# Sheet2.net
KiCad netlist of a schematic drawn in Altium Designer
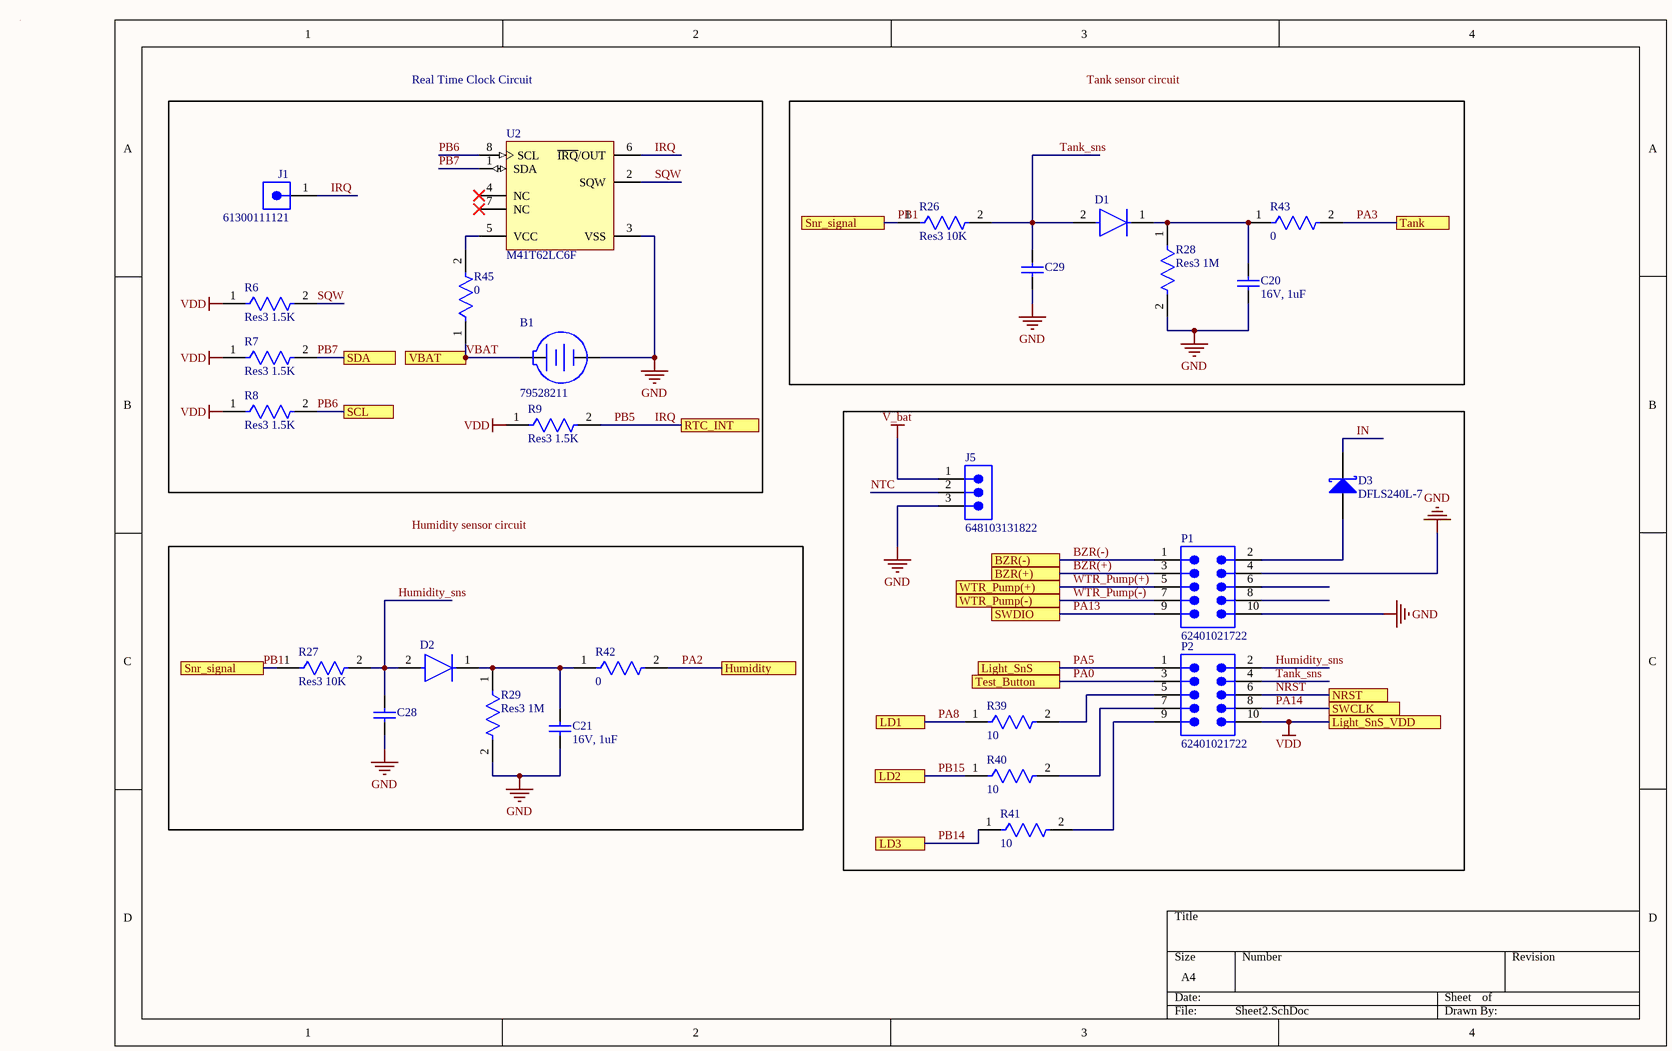
[diagram p0: Sheet2.SchDoc]

(export (version "E")
  (design (tool "Eeschema 10.0.6"))
  (components
    (comp (ref "B1")
      (value "79528211")
      (footprint "79528211")
      (description "Battery Holder, 2025/2032, Th Rohs Compliant: Yes")
      (libsource (lib "Altium Content Vault") (part "Battery Holder"))
    )
    (comp (ref "C20")
      (value "16V, 1uF")
      (footprint "CAPC1608X90X35NL15T15")
      (fields
        (field (name "MANUFACTURER") "AVX Interconnect / Elco")
        (field (name "PART NUMBER") "0603YC105JAT2A")
      )
      (libsource (lib "Altium Content Vault") (part "CAP"))
    )
    (comp (ref "C21")
      (value "16V, 1uF")
      (footprint "CAPC1608X90X35NL15T15")
      (fields
        (field (name "MANUFACTURER") "AVX Interconnect / Elco")
        (field (name "PART NUMBER") "0603YC105JAT2A")
      )
      (libsource (lib "Altium Content Vault") (part "CAP"))
    )
    (comp (ref "C28")
      (value "16V, 1uF")
      (footprint "CAPC1608X90X35NL15T15")
      (fields
        (field (name "MANUFACTURER") "AVX Interconnect / Elco")
        (field (name "PART NUMBER") "0603YC105JAT2A")
      )
      (libsource (lib "Altium Content Vault") (part "CAP"))
    )
    (comp (ref "C29")
      (value "16V, 1uF")
      (footprint "CAPC1608X90X35NL15T15")
      (fields
        (field (name "MANUFACTURER") "AVX Interconnect / Elco")
        (field (name "PART NUMBER") "0603YC105JAT2A")
      )
      (libsource (lib "Altium Content Vault") (part "CAP"))
    )
    (comp (ref "D1")
      (value "1N4148WS-HG3-08")
      (footprint "FP-S8-V-3910_02-001-MFG")
      (description "DIODE GEN PURP 100V 150MA SOD323")
      (libsource (lib "Altium Content Vault") (part "d7152d700b627762746794eb795d46e"))
    )
    (comp (ref "D2")
      (value "1N4148WS-HG3-08")
      (footprint "FP-S8-V-3910_02-001-MFG")
      (description "DIODE GEN PURP 100V 150MA SOD323")
      (libsource (lib "Altium Content Vault") (part "d7152d700b627762746794eb795d46e"))
    )
    (comp (ref "D3")
      (value "DFLS240L-7")
      (footprint "DIOD-POWERDI123-2_A_V")
      (description "Low VF Schottky Barrier Rectifier, 2 A, 40 V, -55 to 125 degC, 2-Pin SMD, RoHS, Tape and Reel")
      (fields (field (name "MANUFACTURER") "Diodes Inc"))
      (libsource (lib "Altium Content Vault") (part "DSKY-AK-2"))
    )
    (comp (ref "J1")
      (value "61300111121")
      (footprint "61300111121")
      (description "THT Vertical Pin Header WR-PHD, Pitch 2.54 mm, Single Row, 1 pins")
      (libsource (lib "Altium Content Vault") (part "Header_Male_1R_01P"))
    )
    (comp (ref "J5")
      (value "648103131822")
      (footprint "648103131822")
      (description "Wr-wtb; 1.5MM Pitch 3 Way 1 Row Shrouded Straight Pcb Header, Through Hole")
      (libsource (lib "Altium Content Vault") (part "Header_Male_1R_03P"))
    )
    (comp (ref "P1")
      (value "62401021722")
      (footprint "62401021722")
      (description "WR-WTB Wire-to-Board Connectors 2.00 mm")
      (libsource (lib "Altium Content Vault") (part "Header_Male_2R_10P"))
    )
    (comp (ref "P2")
      (value "62401021722")
      (footprint "62401021722")
      (description "WR-WTB Wire-to-Board Connectors 2.00 mm")
      (libsource (lib "Altium Content Vault") (part "Header_Male_2R_10P"))
    )
    (comp (ref "R6")
      (value "Res3 1.5K")
      (footprint "FP-AC0603-IPC_B")
      (description "RES 1.5kΩ 1.00% 0.2W 0603")
      (libsource (lib "Altium Content Vault") (part "1029c3af85768c4190bb7ad29bc67b5"))
    )
    (comp (ref "R7")
      (value "Res3 1.5K")
      (footprint "FP-AC0603-MFG")
      (description "RES 1.5kΩ 1.00% 0.2W 0603")
      (libsource (lib "Altium Content Vault") (part "1029c3af85768c4190bb7ad29bc67b5"))
    )
    (comp (ref "R8")
      (value "Res3 1.5K")
      (footprint "FP-AC0603-MFG")
      (description "RES 1.5kΩ 1.00% 0.2W 0603")
      (libsource (lib "Altium Content Vault") (part "1029c3af85768c4190bb7ad29bc67b5"))
    )
    (comp (ref "R9")
      (value "Res3 1.5K")
      (footprint "FP-AC0603-MFG")
      (description "RES 1.5kΩ 1.00% 0.2W 0603")
      (libsource (lib "Altium Content Vault") (part "1029c3af85768c4190bb7ad29bc67b5"))
    )
    (comp (ref "R26")
      (value "Res3 10K")
      (footprint "FP-AC0603-MFG")
      (description "RES 10kΩ 1.00% 0.2W 0603")
      (libsource (lib "Altium Content Vault") (part "1029c3af85768c4190bb7ad29bc67b5"))
    )
    (comp (ref "R27")
      (value "Res3 10K")
      (footprint "FP-AC0603-MFG")
      (description "RES 10kΩ 1.00% 0.2W 0603")
      (libsource (lib "Altium Content Vault") (part "1029c3af85768c4190bb7ad29bc67b5"))
    )
    (comp (ref "R28")
      (value "Res3 1M")
      (footprint "FP-CRGP0603-IPC_C")
      (description "RES 1M OHM 1% 1/4W 0603")
      (fields (field (name "TOLERANCE") "1%"))
      (libsource (lib "Altium Content Vault") (part "1029c3af85768c4190bb7ad29bc67b5"))
    )
    (comp (ref "R29")
      (value "Res3 1M")
      (footprint "FP-CRGP0603-IPC_C")
      (description "RES 1M OHM 1% 1/4W 0603")
      (fields (field (name "TOLERANCE") "1%"))
      (libsource (lib "Altium Content Vault") (part "1029c3af85768c4190bb7ad29bc67b5"))
    )
    (comp (ref "R39")
      (value "10")
      (footprint "FP-AC0603-MFG")
      (description "RES 10kΩ 5.00% 0.1W 0603")
      (fields (field (name "TOLERANCE") "5%"))
      (libsource (lib "Altium Content Vault") (part "1029c3af85768c4190bb7ad29bc67b5"))
    )
    (comp (ref "R40")
      (value "10")
      (footprint "FP-AC0603-MFG")
      (description "RES 10kΩ 5.00% 0.1W 0603")
      (fields (field (name "TOLERANCE") "5%"))
      (libsource (lib "Altium Content Vault") (part "1029c3af85768c4190bb7ad29bc67b5"))
    )
    (comp (ref "R41")
      (value "10")
      (footprint "FP-AC0603-MFG")
      (description "RES 10kΩ 5.00% 0.1W 0603")
      (fields (field (name "TOLERANCE") "5%"))
      (libsource (lib "Altium Content Vault") (part "1029c3af85768c4190bb7ad29bc67b5"))
    )
    (comp (ref "R42")
      (value "0")
      (footprint "FP-CRCW0603-MFG")
      (description "RES SMD 0 OHM JUMPER 1/10W 0603")
      (fields (field (name "TOLERANCE") "5%"))
      (libsource (lib "Altium Content Vault") (part "1029c3af85768c4190bb7ad29bc67b5"))
    )
    (comp (ref "R43")
      (value "0")
      (footprint "FP-CRCW0603-MFG")
      (description "RES SMD 0 OHM JUMPER 1/10W 0603")
      (fields (field (name "TOLERANCE") "5%"))
      (libsource (lib "Altium Content Vault") (part "1029c3af85768c4190bb7ad29bc67b5"))
    )
    (comp (ref "R45")
      (value "0")
      (footprint "FP-CRCW0603-MFG")
      (description "RES SMD 0 OHM JUMPER 1/10W 0603")
      (fields (field (name "TOLERANCE") "5%"))
      (libsource (lib "Altium Content Vault") (part "1029c3af85768c4190bb7ad29bc67b5"))
    )
    (comp (ref "U2")
      (value "M41T62LC6F")
      (footprint "STM-LCC8_V")
      (fields (field (name "MANUFACTURER") "STMicroelectronics"))
      (libsource (lib "Altium Content Vault") (part "STM-M41T62-LCC8"))
    )
  )
  (nets
    (net (code "1") (name "/BZR(+)") (class "Default")
      (node (ref "P1") (pin "3") (pinfunction "3_3") (pintype "passive"))
    )
    (net (code "2") (name "/BZR(-)") (class "Default")
      (node (ref "P1") (pin "1") (pinfunction "1_1") (pintype "passive"))
    )
    (net (code "4") (name "/Humidity_sns") (class "Default")
      (node (ref "C28") (pin "2") (pinfunction "2_2") (pintype "passive"))
      (node (ref "D2") (pin "2") (pinfunction "A_2") (pintype "passive"))
      (node (ref "P2") (pin "2") (pinfunction "2_2") (pintype "passive"))
      (node (ref "R27") (pin "2") (pinfunction "2_2") (pintype "passive"))
    )
    (net (code "5") (name "/IN") (class "Default")
      (node (ref "D3") (pin "2") (pinfunction "K_2") (pintype "passive"))
    )
    (net (code "6") (name "/IRQ") (class "Default")
      (node (ref "J1") (pin "1") (pinfunction "1_1") (pintype "passive"))
      (node (ref "R9") (pin "2") (pinfunction "2_2") (pintype "passive"))
      (node (ref "U2") (pin "6") (pinfunction "~{IRQ}/OUT_6") (pintype "passive"))
    )
    (net (code "7") (name "/NRST") (class "Default")
      (node (ref "P2") (pin "6") (pinfunction "6_6") (pintype "passive"))
    )
    (net (code "8") (name "/NTC") (class "Default")
      (node (ref "J5") (pin "2") (pinfunction "2_2") (pintype "passive"))
    )
    (net (code "9") (name "/PA0") (class "Default")
      (node (ref "P2") (pin "3") (pinfunction "3_3") (pintype "passive"))
    )
    (net (code "10") (name "/PA2") (class "Default")
      (node (ref "R42") (pin "2") (pinfunction "2_2") (pintype "passive"))
    )
    (net (code "11") (name "/PA3") (class "Default")
      (node (ref "R43") (pin "2") (pinfunction "2_2") (pintype "passive"))
    )
    (net (code "12") (name "/PA5") (class "Default")
      (node (ref "P2") (pin "1") (pinfunction "1_1") (pintype "passive"))
    )
    (net (code "13") (name "/PA8") (class "Default")
      (node (ref "R39") (pin "1") (pinfunction "1_1") (pintype "passive"))
    )
    (net (code "14") (name "/PA13") (class "Default")
      (node (ref "P1") (pin "9") (pinfunction "9_9") (pintype "passive"))
    )
    (net (code "15") (name "/PA14") (class "Default")
      (node (ref "P2") (pin "8") (pinfunction "8_8") (pintype "passive"))
    )
    (net (code "16") (name "/PB1") (class "Default")
      (node (ref "R26") (pin "1") (pinfunction "1_1") (pintype "passive"))
      (node (ref "R27") (pin "1") (pinfunction "1_1") (pintype "passive"))
    )
    (net (code "17") (name "/PB6") (class "Default")
      (node (ref "R8") (pin "2") (pinfunction "2_2") (pintype "passive"))
      (node (ref "U2") (pin "8") (pinfunction "SCL_8") (pintype "input"))
    )
    (net (code "18") (name "/PB7") (class "Default")
      (node (ref "R7") (pin "2") (pinfunction "2_2") (pintype "passive"))
      (node (ref "U2") (pin "1") (pinfunction "SDA_1") (pintype "bidirectional"))
    )
    (net (code "19") (name "/PB14") (class "Default")
      (node (ref "R41") (pin "1") (pinfunction "1_1") (pintype "passive"))
    )
    (net (code "20") (name "/PB15") (class "Default")
      (node (ref "R40") (pin "1") (pinfunction "1_1") (pintype "passive"))
    )
    (net (code "21") (name "/SQW") (class "Default")
      (node (ref "R6") (pin "2") (pinfunction "2_2") (pintype "passive"))
      (node (ref "U2") (pin "2") (pinfunction "SQW_2") (pintype "passive"))
    )
    (net (code "23") (name "/Tank_sns") (class "Default")
      (node (ref "C29") (pin "2") (pinfunction "2_2") (pintype "passive"))
      (node (ref "D1") (pin "2") (pinfunction "A_2") (pintype "passive"))
      (node (ref "P2") (pin "4") (pinfunction "4_4") (pintype "passive"))
      (node (ref "R26") (pin "2") (pinfunction "2_2") (pintype "passive"))
    )
    (net (code "24") (name "/VBAT") (class "Default")
      (node (ref "B1") (pin "1") (pinfunction "+_1") (pintype "passive"))
      (node (ref "R45") (pin "1") (pinfunction "1_1") (pintype "passive"))
    )
    (net (code "25") (name "/WTR_Pump(+)") (class "Default")
      (node (ref "P1") (pin "5") (pinfunction "5_5") (pintype "passive"))
    )
    (net (code "26") (name "/WTR_Pump(-)") (class "Default")
      (node (ref "P1") (pin "7") (pinfunction "7_7") (pintype "passive"))
    )
    (net (code "27") (name "GND") (class "Default")
      (node (ref "B1") (pin "2") (pinfunction "-_2") (pintype "passive"))
      (node (ref "C20") (pin "1") (pinfunction "1_1") (pintype "passive"))
      (node (ref "C21") (pin "1") (pinfunction "1_1") (pintype "passive"))
      (node (ref "C28") (pin "1") (pinfunction "1_1") (pintype "passive"))
      (node (ref "C29") (pin "1") (pinfunction "1_1") (pintype "passive"))
      (node (ref "J5") (pin "3") (pinfunction "3_3") (pintype "passive"))
      (node (ref "P1") (pin "10") (pinfunction "10_10") (pintype "passive"))
      (node (ref "P1") (pin "4") (pinfunction "4_4") (pintype "passive"))
      (node (ref "R28") (pin "2") (pinfunction "2_2") (pintype "passive"))
      (node (ref "R29") (pin "2") (pinfunction "2_2") (pintype "passive"))
      (node (ref "U2") (pin "3") (pinfunction "VSS_3") (pintype "power_in"))
    )
    (net (code "28") (name "Net-(D1-C)") (class "Default")
      (node (ref "C20") (pin "2") (pinfunction "2_2") (pintype "passive"))
      (node (ref "D1") (pin "1") (pinfunction "C_1") (pintype "passive"))
      (node (ref "R28") (pin "1") (pinfunction "1_1") (pintype "passive"))
      (node (ref "R43") (pin "1") (pinfunction "1_1") (pintype "passive"))
    )
    (net (code "29") (name "Net-(D2-C)") (class "Default")
      (node (ref "C21") (pin "2") (pinfunction "2_2") (pintype "passive"))
      (node (ref "D2") (pin "1") (pinfunction "C_1") (pintype "passive"))
      (node (ref "R29") (pin "1") (pinfunction "1_1") (pintype "passive"))
      (node (ref "R42") (pin "1") (pinfunction "1_1") (pintype "passive"))
    )
    (net (code "30") (name "Net-(D3-A)") (class "Default")
      (node (ref "D3") (pin "1") (pinfunction "A_1") (pintype "passive"))
      (node (ref "P1") (pin "2") (pinfunction "2_2") (pintype "passive"))
    )
    (net (code "31") (name "Net-(P2-Pad5)") (class "Default")
      (node (ref "P2") (pin "5") (pinfunction "5_5") (pintype "passive"))
      (node (ref "R39") (pin "2") (pinfunction "2_2") (pintype "passive"))
    )
    (net (code "32") (name "Net-(P2-Pad7)") (class "Default")
      (node (ref "P2") (pin "7") (pinfunction "7_7") (pintype "passive"))
      (node (ref "R40") (pin "2") (pinfunction "2_2") (pintype "passive"))
    )
    (net (code "33") (name "Net-(P2-Pad9)") (class "Default")
      (node (ref "P2") (pin "9") (pinfunction "9_9") (pintype "passive"))
      (node (ref "R41") (pin "2") (pinfunction "2_2") (pintype "passive"))
    )
    (net (code "34") (name "Net-(U2-VCC)") (class "Default")
      (node (ref "R45") (pin "2") (pinfunction "2_2") (pintype "passive"))
      (node (ref "U2") (pin "5") (pinfunction "VCC_5") (pintype "power_in"))
    )
    (net (code "35") (name "VDD") (class "Default")
      (node (ref "P2") (pin "10") (pinfunction "10_10") (pintype "passive"))
      (node (ref "R6") (pin "1") (pinfunction "1_1") (pintype "passive"))
      (node (ref "R7") (pin "1") (pinfunction "1_1") (pintype "passive"))
      (node (ref "R8") (pin "1") (pinfunction "1_1") (pintype "passive"))
      (node (ref "R9") (pin "1") (pinfunction "1_1") (pintype "passive"))
    )
    (net (code "36") (name "V_bat") (class "Default")
      (node (ref "J5") (pin "1") (pinfunction "1_1") (pintype "passive"))
    )
    (net (code "37") (name "unconnected-(P1-Pad6)") (class "Default")
      (node (ref "P1") (pin "6") (pinfunction "6_6") (pintype "passive"))
    )
    (net (code "38") (name "unconnected-(P1-Pad8)") (class "Default")
      (node (ref "P1") (pin "8") (pinfunction "8_8") (pintype "passive"))
    )
    (net (code "39") (name "unconnected-(U2-NC-Pad4)") (class "Default")
      (node (ref "U2") (pin "4") (pinfunction "NC_4") (pintype "passive+no_connect"))
    )
    (net (code "40") (name "unconnected-(U2-NC-Pad7)") (class "Default")
      (node (ref "U2") (pin "7") (pinfunction "NC_7") (pintype "passive+no_connect"))
    )
  )
)
